# MotionSense.net
KiCad netlist of a schematic drawn in EAGLE
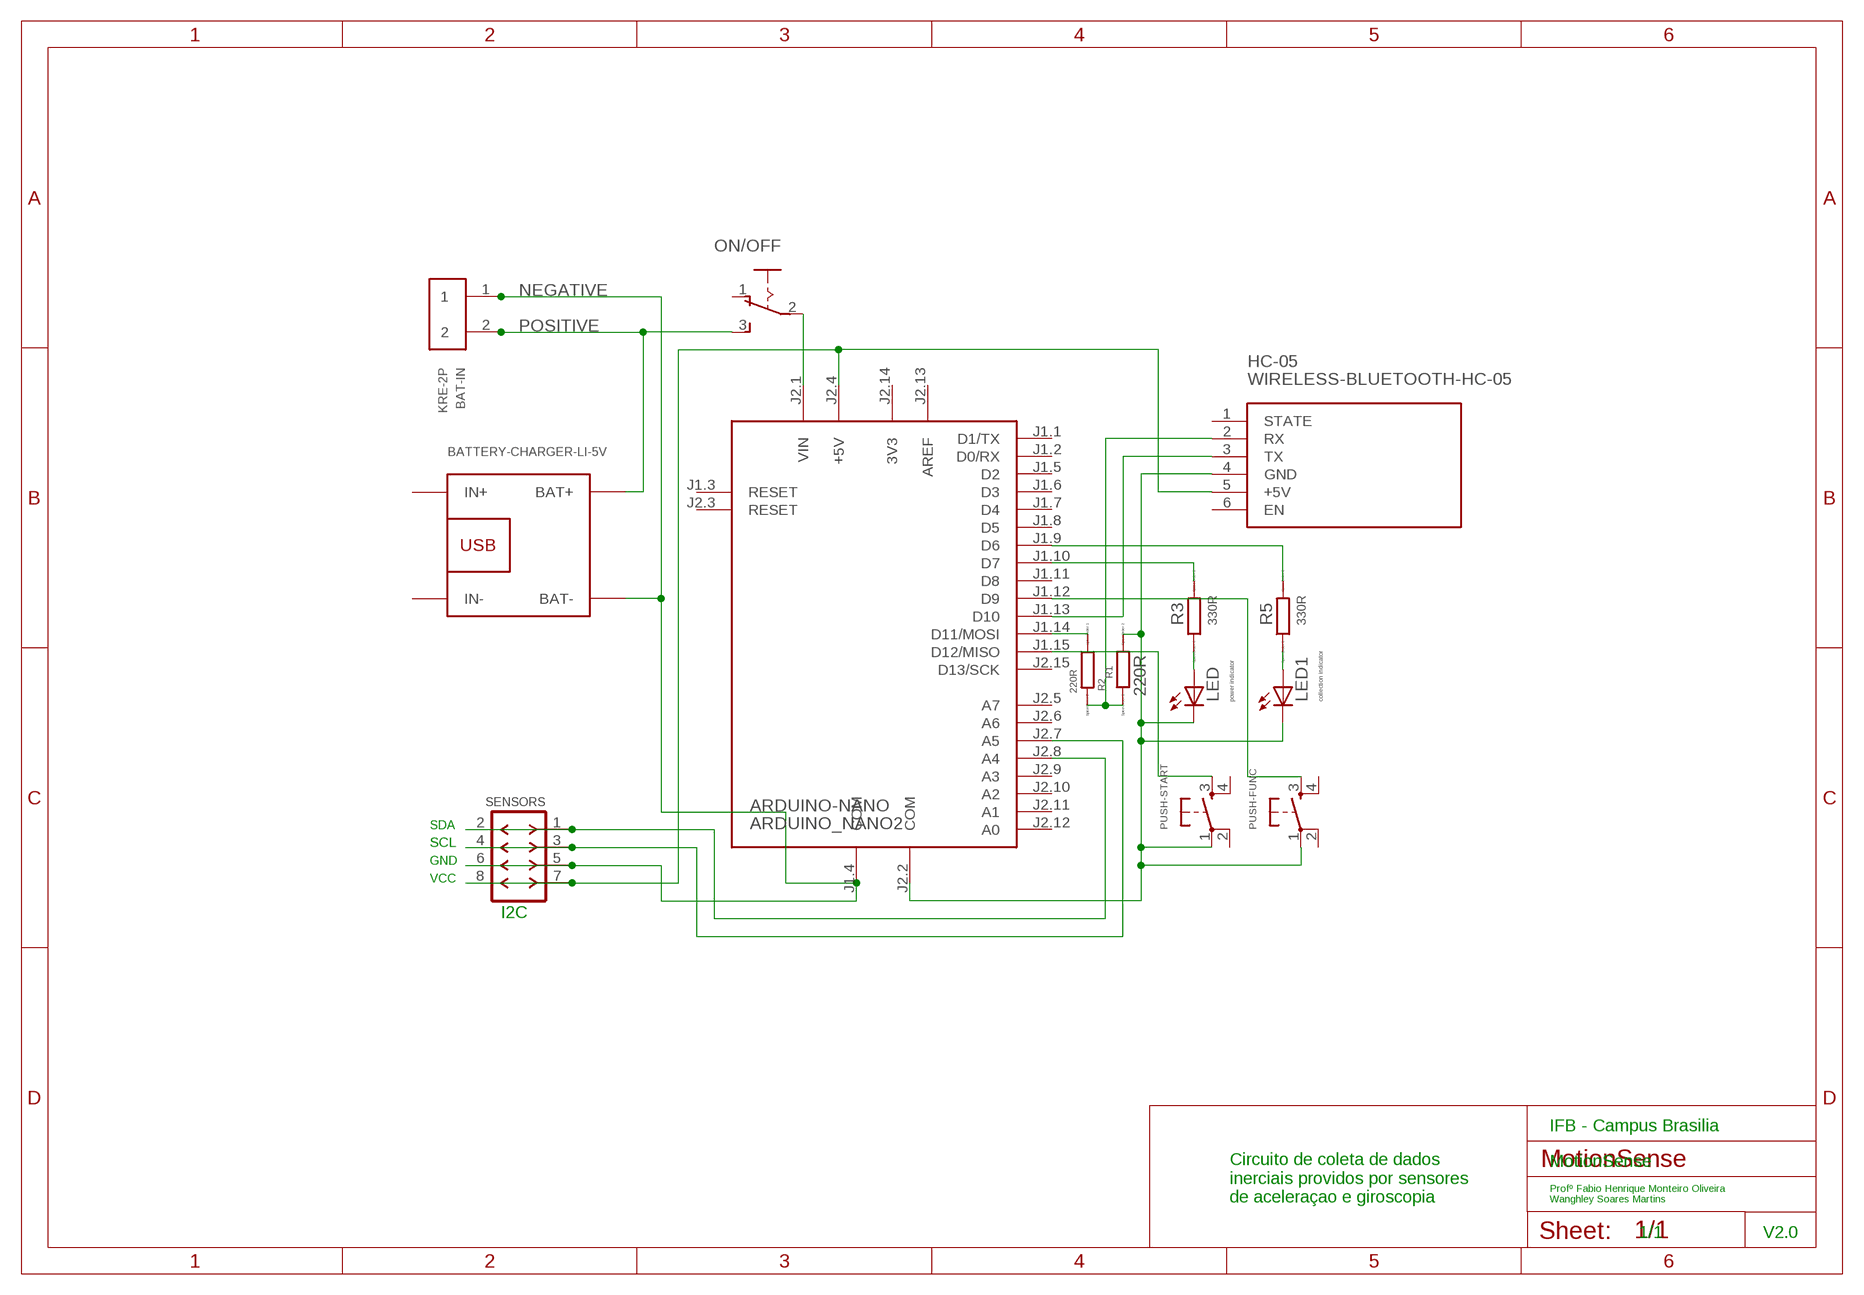
[diagram p0: schematic, sheet 1]

(export (version "E")
  (design (tool "Eeschema 10.0.6"))
  (components
    (comp (ref "ARDUINO-NANO")
      (value "ARDUINO_NANO2")
      (footprint "eagle-import:ARDUINO_NANO2")
      (libsource (lib "eagle-import") (part "ARDUINO_NANO2"))
    )
    (comp (ref "BAT-IN")
      (value "KRE-2P")
      (footprint "eagle-import:KRE-2P")
      (libsource (lib "eagle-import") (part "KRE-2P"))
    )
    (comp (ref "HC-05")
      (value "WIRELESS-BLUETOOTH-HC-05")
      (footprint "eagle-import:WIRELESS-BLUETOOTH-HC-05")
      (libsource (lib "eagle-import") (part "WIRELESS-BLUETOOTH-HC-05"))
    )
    (comp (ref "LED")
      (value "power indicator")
      (footprint "eagle-import:LED5MM")
      (libsource (lib "eagle-import") (part "LED5MM"))
    )
    (comp (ref "LED1")
      (value "collection indicator")
      (footprint "eagle-import:LED5MM")
      (libsource (lib "eagle-import") (part "LED5MM"))
    )
    (comp (ref "ON/OFF")
      (value "255SB")
      (footprint "eagle-import:255SB")
      (libsource (lib "eagle-import") (part "255SB"))
    )
    (comp (ref "PUSH-FUNC")
      (value "DTS-6")
      (footprint "eagle-import:DTS-6")
      (libsource (lib "eagle-import") (part "DTS-6"))
    )
    (comp (ref "PUSH-START")
      (value "DTS-6")
      (footprint "eagle-import:DTS-6")
      (libsource (lib "eagle-import") (part "DTS-6"))
    )
    (comp (ref "R1")
      (value "220R")
      (footprint "eagle-import:0207_10")
      (libsource (lib "eagle-import") (part "R0207/10"))
    )
    (comp (ref "R2")
      (value "220R")
      (footprint "eagle-import:0207_10")
      (libsource (lib "eagle-import") (part "R0207/10"))
    )
    (comp (ref "R3")
      (value "330R")
      (footprint "eagle-import:0207_10")
      (libsource (lib "eagle-import") (part "R0207/10"))
    )
    (comp (ref "R5")
      (value "330R")
      (footprint "eagle-import:0207_10")
      (libsource (lib "eagle-import") (part "R0207/10"))
    )
    (comp (ref "SENSORS")
      (value "F-2X04-DIL-2MM_M")
      (footprint "eagle-import:DIL-2MM-2X04_M")
      (libsource (lib "eagle-import") (part "F-2X04-DIL-2MM_M"))
    )
    (comp (ref "U$1")
      (value "BATTERY-CHARGER-LI-5V")
      (footprint "eagle-import:BATTERY-CHARGER-LI-5V")
      (libsource (lib "eagle-import") (part "BATTERY-CHARGER-LI-5V"))
    )
  )
  (nets
    (net (code "1") (name "/3V3") (class "Default")
      (node (ref "ARDUINO-NANO") (pin "J2.14") (pinfunction "3V3_J2.14") (pintype "power_in"))
    )
    (net (code "2") (name "/AREF") (class "Default")
      (node (ref "ARDUINO-NANO") (pin "J2.13") (pinfunction "AREF_J2.13") (pintype "power_in"))
    )
    (net (code "3") (name "/NEGATIVE") (class "Default")
      (node (ref "ARDUINO-NANO") (pin "J1.4") (pinfunction "COM_J1.4") (pintype "power_in"))
      (node (ref "BAT-IN") (pin "1") (pinfunction "1_1") (pintype "bidirectional"))
      (node (ref "SENSORS") (pin "5") (pinfunction "5_5") (pintype "passive"))
      (node (ref "SENSORS") (pin "6") (pinfunction "6_6") (pintype "passive"))
      (node (ref "U$1") (pin "BAT-") (pinfunction "BAT-_BAT-") (pintype "bidirectional"))
    )
    (net (code "4") (name "/POSITIVE") (class "Default")
      (node (ref "BAT-IN") (pin "2") (pinfunction "2_2") (pintype "bidirectional"))
      (node (ref "ON/OFF") (pin "3") (pinfunction "S_3") (pintype "passive"))
      (node (ref "U$1") (pin "BAT+") (pinfunction "BAT+_BAT+") (pintype "bidirectional"))
    )
    (net (code "5") (name "Net-(ARDUINO-NANO-+5V)") (class "Default")
      (node (ref "ARDUINO-NANO") (pin "J2.4") (pinfunction "+5V_J2.4") (pintype "power_in"))
      (node (ref "HC-05") (pin "5") (pinfunction "+5V_5") (pintype "power_in"))
      (node (ref "SENSORS") (pin "7") (pinfunction "7_7") (pintype "passive"))
      (node (ref "SENSORS") (pin "8") (pinfunction "8_8") (pintype "passive"))
    )
    (net (code "6") (name "Net-(ARDUINO-NANO-A4)") (class "Default")
      (node (ref "ARDUINO-NANO") (pin "J2.8") (pinfunction "A4_J2.8") (pintype "bidirectional"))
      (node (ref "SENSORS") (pin "1") (pinfunction "1_1") (pintype "passive"))
      (node (ref "SENSORS") (pin "2") (pinfunction "2_2") (pintype "passive"))
    )
    (net (code "7") (name "Net-(ARDUINO-NANO-A5)") (class "Default")
      (node (ref "ARDUINO-NANO") (pin "J2.7") (pinfunction "A5_J2.7") (pintype "bidirectional"))
      (node (ref "SENSORS") (pin "3") (pinfunction "3_3") (pintype "passive"))
      (node (ref "SENSORS") (pin "4") (pinfunction "4_4") (pintype "passive"))
    )
    (net (code "8") (name "Net-(ARDUINO-NANO-D6)") (class "Default")
      (node (ref "ARDUINO-NANO") (pin "J1.9") (pinfunction "D6_J1.9") (pintype "bidirectional"))
      (node (ref "R5") (pin "2") (pinfunction "2_2") (pintype "passive"))
    )
    (net (code "9") (name "Net-(ARDUINO-NANO-D7)") (class "Default")
      (node (ref "ARDUINO-NANO") (pin "J1.10") (pinfunction "D7_J1.10") (pintype "bidirectional"))
      (node (ref "R3") (pin "2") (pinfunction "2_2") (pintype "passive"))
    )
    (net (code "10") (name "Net-(ARDUINO-NANO-D9)") (class "Default")
      (node (ref "ARDUINO-NANO") (pin "J1.12") (pinfunction "D9_J1.12") (pintype "bidirectional"))
      (node (ref "PUSH-FUNC") (pin "3") (pinfunction "3_3") (pintype "passive"))
    )
    (net (code "11") (name "Net-(ARDUINO-NANO-D10)") (class "Default")
      (node (ref "ARDUINO-NANO") (pin "J1.13") (pinfunction "D10_J1.13") (pintype "bidirectional"))
      (node (ref "HC-05") (pin "3") (pinfunction "TX_3") (pintype "bidirectional"))
    )
    (net (code "12") (name "Net-(ARDUINO-NANO-D11{slash}MOSI)") (class "Default")
      (node (ref "ARDUINO-NANO") (pin "J1.14") (pinfunction "D11/MOSI_J1.14") (pintype "bidirectional"))
      (node (ref "R2") (pin "1") (pinfunction "1_1") (pintype "passive"))
    )
    (net (code "13") (name "Net-(ARDUINO-NANO-D12{slash}MISO)") (class "Default")
      (node (ref "ARDUINO-NANO") (pin "J1.15") (pinfunction "D12/MISO_J1.15") (pintype "bidirectional"))
      (node (ref "PUSH-START") (pin "3") (pinfunction "3_3") (pintype "passive"))
    )
    (net (code "14") (name "Net-(ARDUINO-NANO-VIN)") (class "Default")
      (node (ref "ARDUINO-NANO") (pin "J2.1") (pinfunction "VIN_J2.1") (pintype "power_in"))
      (node (ref "ON/OFF") (pin "2") (pinfunction "P_2") (pintype "passive"))
    )
    (net (code "15") (name "Net-(HC-05-GND)") (class "Default")
      (node (ref "ARDUINO-NANO") (pin "J2.2") (pinfunction "COM_J2.2") (pintype "power_in"))
      (node (ref "HC-05") (pin "4") (pinfunction "GND_4") (pintype "power_in"))
      (node (ref "LED") (pin "K") (pinfunction "C_K") (pintype "passive"))
      (node (ref "LED1") (pin "K") (pinfunction "C_K") (pintype "passive"))
      (node (ref "PUSH-FUNC") (pin "1") (pinfunction "1_1") (pintype "passive"))
      (node (ref "PUSH-START") (pin "1") (pinfunction "1_1") (pintype "passive"))
      (node (ref "R1") (pin "2") (pinfunction "2_2") (pintype "passive"))
    )
    (net (code "16") (name "Net-(HC-05-RX)") (class "Default")
      (node (ref "HC-05") (pin "2") (pinfunction "RX_2") (pintype "bidirectional"))
      (node (ref "R1") (pin "1") (pinfunction "1_1") (pintype "passive"))
      (node (ref "R2") (pin "2") (pinfunction "2_2") (pintype "passive"))
    )
    (net (code "17") (name "Net-(LED-PadA)") (class "Default")
      (node (ref "LED") (pin "A") (pinfunction "A_A") (pintype "passive"))
      (node (ref "R3") (pin "1") (pinfunction "1_1") (pintype "passive"))
    )
    (net (code "18") (name "Net-(LED1-PadA)") (class "Default")
      (node (ref "LED1") (pin "A") (pinfunction "A_A") (pintype "passive"))
      (node (ref "R5") (pin "1") (pinfunction "1_1") (pintype "passive"))
    )
    (net (code "19") (name "unconnected-(ARDUINO-NANO-A0-PadJ2.12)") (class "Default")
      (node (ref "ARDUINO-NANO") (pin "J2.12") (pinfunction "A0_J2.12") (pintype "bidirectional"))
    )
    (net (code "20") (name "unconnected-(ARDUINO-NANO-A1-PadJ2.11)") (class "Default")
      (node (ref "ARDUINO-NANO") (pin "J2.11") (pinfunction "A1_J2.11") (pintype "bidirectional"))
    )
    (net (code "21") (name "unconnected-(ARDUINO-NANO-A2-PadJ2.10)") (class "Default")
      (node (ref "ARDUINO-NANO") (pin "J2.10") (pinfunction "A2_J2.10") (pintype "bidirectional"))
    )
    (net (code "22") (name "unconnected-(ARDUINO-NANO-A3-PadJ2.9)") (class "Default")
      (node (ref "ARDUINO-NANO") (pin "J2.9") (pinfunction "A3_J2.9") (pintype "bidirectional"))
    )
    (net (code "23") (name "unconnected-(ARDUINO-NANO-A6-PadJ2.6)") (class "Default")
      (node (ref "ARDUINO-NANO") (pin "J2.6") (pinfunction "A6_J2.6") (pintype "bidirectional"))
    )
    (net (code "24") (name "unconnected-(ARDUINO-NANO-A7-PadJ2.5)") (class "Default")
      (node (ref "ARDUINO-NANO") (pin "J2.5") (pinfunction "A7_J2.5") (pintype "bidirectional"))
    )
    (net (code "25") (name "unconnected-(ARDUINO-NANO-D0{slash}RX-PadJ1.2)") (class "Default")
      (node (ref "ARDUINO-NANO") (pin "J1.2") (pinfunction "D0/RX_J1.2") (pintype "bidirectional"))
    )
    (net (code "26") (name "unconnected-(ARDUINO-NANO-D1{slash}TX-PadJ1.1)") (class "Default")
      (node (ref "ARDUINO-NANO") (pin "J1.1") (pinfunction "D1/TX_J1.1") (pintype "bidirectional"))
    )
    (net (code "27") (name "unconnected-(ARDUINO-NANO-D2-PadJ1.5)") (class "Default")
      (node (ref "ARDUINO-NANO") (pin "J1.5") (pinfunction "D2_J1.5") (pintype "bidirectional"))
    )
    (net (code "28") (name "unconnected-(ARDUINO-NANO-D3-PadJ1.6)") (class "Default")
      (node (ref "ARDUINO-NANO") (pin "J1.6") (pinfunction "D3_J1.6") (pintype "bidirectional"))
    )
    (net (code "29") (name "unconnected-(ARDUINO-NANO-D4-PadJ1.7)") (class "Default")
      (node (ref "ARDUINO-NANO") (pin "J1.7") (pinfunction "D4_J1.7") (pintype "bidirectional"))
    )
    (net (code "30") (name "unconnected-(ARDUINO-NANO-D5-PadJ1.8)") (class "Default")
      (node (ref "ARDUINO-NANO") (pin "J1.8") (pinfunction "D5_J1.8") (pintype "bidirectional"))
    )
    (net (code "31") (name "unconnected-(ARDUINO-NANO-D8-PadJ1.11)") (class "Default")
      (node (ref "ARDUINO-NANO") (pin "J1.11") (pinfunction "D8_J1.11") (pintype "bidirectional"))
    )
    (net (code "32") (name "unconnected-(ARDUINO-NANO-D13{slash}SCK-PadJ2.15)") (class "Default")
      (node (ref "ARDUINO-NANO") (pin "J2.15") (pinfunction "D13/SCK_J2.15") (pintype "bidirectional"))
    )
    (net (code "33") (name "unconnected-(ARDUINO-NANO-RESET-PadJ1.3)") (class "Default")
      (node (ref "ARDUINO-NANO") (pin "J1.3") (pinfunction "RESET_J1.3") (pintype "bidirectional"))
    )
    (net (code "34") (name "unconnected-(ARDUINO-NANO-RESET-PadJ2.3)") (class "Default")
      (node (ref "ARDUINO-NANO") (pin "J2.3") (pinfunction "RESET_J2.3") (pintype "bidirectional"))
    )
    (net (code "35") (name "unconnected-(HC-05-EN-Pad6)") (class "Default")
      (node (ref "HC-05") (pin "6") (pinfunction "EN_6") (pintype "bidirectional"))
    )
    (net (code "36") (name "unconnected-(HC-05-STATE-Pad1)") (class "Default")
      (node (ref "HC-05") (pin "1") (pinfunction "STATE_1") (pintype "bidirectional"))
    )
    (net (code "37") (name "unconnected-(ON/OFF-O-Pad1)") (class "Default")
      (node (ref "ON/OFF") (pin "1") (pinfunction "O_1") (pintype "passive"))
    )
    (net (code "38") (name "unconnected-(PUSH-FUNC-Pad2)") (class "Default")
      (node (ref "PUSH-FUNC") (pin "2") (pinfunction "2_2") (pintype "passive"))
    )
    (net (code "39") (name "unconnected-(PUSH-FUNC-Pad4)") (class "Default")
      (node (ref "PUSH-FUNC") (pin "4") (pinfunction "4_4") (pintype "passive"))
    )
    (net (code "40") (name "unconnected-(PUSH-START-Pad2)") (class "Default")
      (node (ref "PUSH-START") (pin "2") (pinfunction "2_2") (pintype "passive"))
    )
    (net (code "41") (name "unconnected-(PUSH-START-Pad4)") (class "Default")
      (node (ref "PUSH-START") (pin "4") (pinfunction "4_4") (pintype "passive"))
    )
    (net (code "42") (name "unconnected-(U$1-PadIN+)") (class "Default")
      (node (ref "U$1") (pin "IN+") (pinfunction "IN+_IN+") (pintype "bidirectional"))
    )
    (net (code "43") (name "unconnected-(U$1-PadIN-)") (class "Default")
      (node (ref "U$1") (pin "IN-") (pinfunction "IN-_IN-") (pintype "bidirectional"))
    )
  )
)
